# DSPLIT.net
KiCad netlist of a schematic drawn in EAGLE
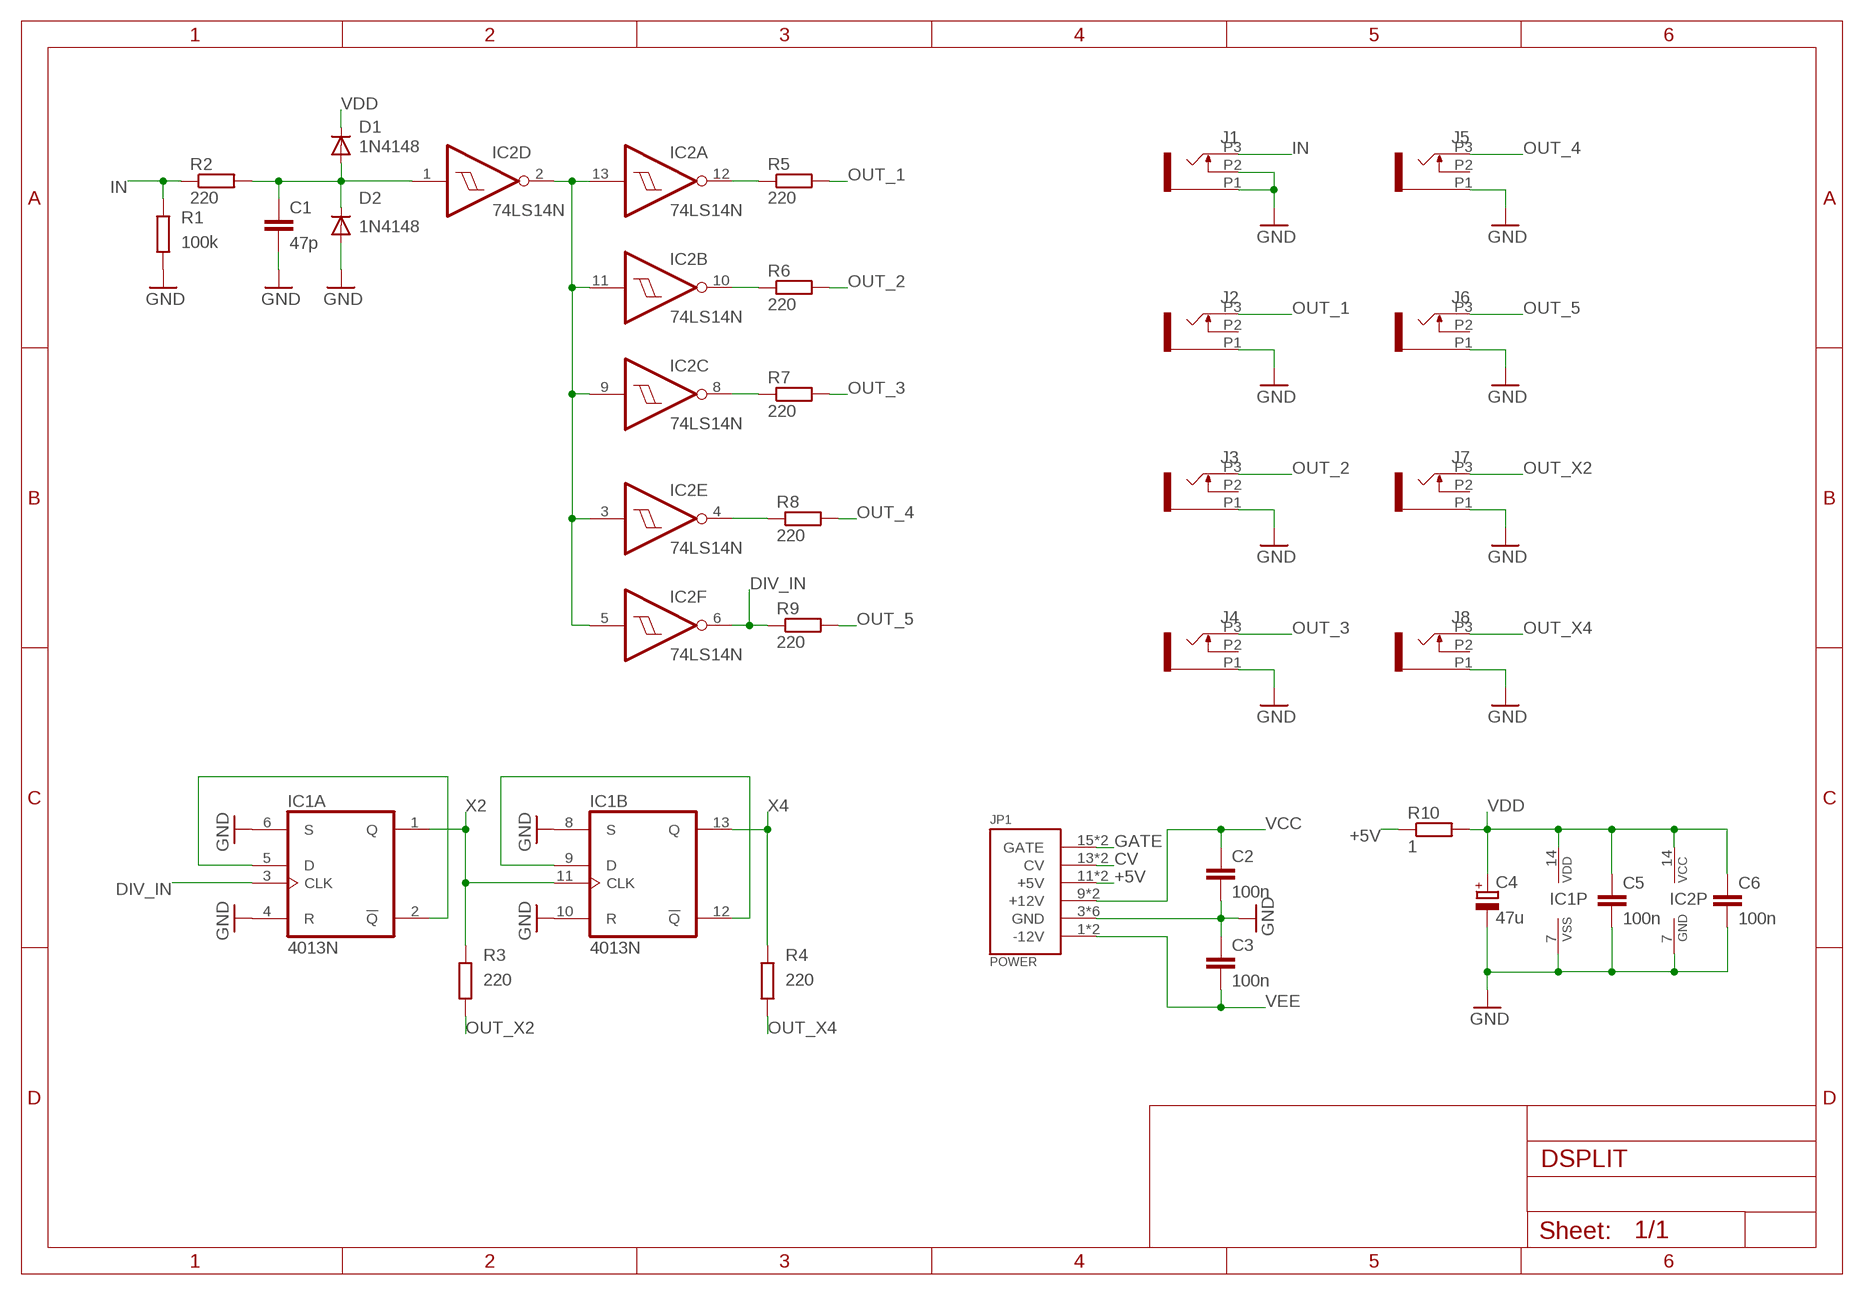
[diagram p0: schematic, sheet 1]

(export (version "E")
  (design (tool "Eeschema 10.0.6"))
  (components
    (comp (ref "C1")
      (value "47p")
      (footprint "eagle-import:C050-024X044")
      (libsource (lib "eagle-import") (part "C-EU050-024X044"))
    )
    (comp (ref "C2")
      (value "100n")
      (footprint "eagle-import:C050-024X044")
      (libsource (lib "eagle-import") (part "C-EU050-024X044"))
    )
    (comp (ref "C3")
      (value "100n")
      (footprint "eagle-import:C050-024X044")
      (libsource (lib "eagle-import") (part "C-EU050-024X044"))
    )
    (comp (ref "C4")
      (value "47u")
      (footprint "eagle-import:E2,5-6")
      (libsource (lib "eagle-import") (part "CPOL-EUE2.5-6"))
    )
    (comp (ref "C5")
      (value "100n")
      (footprint "eagle-import:C050-024X044")
      (libsource (lib "eagle-import") (part "C-EU050-024X044"))
    )
    (comp (ref "C6")
      (value "100n")
      (footprint "eagle-import:C050-024X044")
      (libsource (lib "eagle-import") (part "C-EU050-024X044"))
    )
    (comp (ref "D1")
      (value "1N4148")
      (footprint "eagle-import:DO35-7")
      (libsource (lib "eagle-import") (part "1N4148DO35-7"))
    )
    (comp (ref "D2")
      (value "1N4148")
      (footprint "eagle-import:DO35-7")
      (libsource (lib "eagle-import") (part "1N4148DO35-7"))
    )
    (comp (ref "IC1")
      (value "4013N")
      (footprint "eagle-import:DIL14")
      (libsource (lib "eagle-import") (part "4013N"))
    )
    (comp (ref "IC2")
      (value "74LS14N")
      (footprint "eagle-import:DIL14")
      (libsource (lib "eagle-import") (part "7414NLS"))
    )
    (comp (ref "J1")
      (value "WQP-PJ302M_JACK")
      (footprint "eagle-import:WQP-PJ302M_JACK")
      (libsource (lib "eagle-import") (part "WQP-PJ302M_JACK"))
    )
    (comp (ref "J2")
      (value "WQP-PJ302M_JACK")
      (footprint "eagle-import:WQP-PJ302M_JACK")
      (libsource (lib "eagle-import") (part "WQP-PJ302M_JACK"))
    )
    (comp (ref "J3")
      (value "WQP-PJ302M_JACK")
      (footprint "eagle-import:WQP-PJ302M_JACK")
      (libsource (lib "eagle-import") (part "WQP-PJ302M_JACK"))
    )
    (comp (ref "J4")
      (value "WQP-PJ302M_JACK")
      (footprint "eagle-import:WQP-PJ302M_JACK")
      (libsource (lib "eagle-import") (part "WQP-PJ302M_JACK"))
    )
    (comp (ref "J5")
      (value "WQP-PJ302M_JACK")
      (footprint "eagle-import:WQP-PJ302M_JACK")
      (libsource (lib "eagle-import") (part "WQP-PJ302M_JACK"))
    )
    (comp (ref "J6")
      (value "WQP-PJ302M_JACK")
      (footprint "eagle-import:WQP-PJ302M_JACK")
      (libsource (lib "eagle-import") (part "WQP-PJ302M_JACK"))
    )
    (comp (ref "J7")
      (value "WQP-PJ302M_JACK")
      (footprint "eagle-import:WQP-PJ302M_JACK")
      (libsource (lib "eagle-import") (part "WQP-PJ302M_JACK"))
    )
    (comp (ref "J8")
      (value "WQP-PJ302M_JACK")
      (footprint "eagle-import:WQP-PJ302M_JACK")
      (libsource (lib "eagle-import") (part "WQP-PJ302M_JACK"))
    )
    (comp (ref "JP1")
      (value "POWER")
      (footprint "eagle-import:POWER_16")
      (libsource (lib "eagle-import") (part "POWER{dblquote}"))
    )
    (comp (ref "R1")
      (value "100k")
      (footprint "eagle-import:0204_7")
      (libsource (lib "eagle-import") (part "R-EU_0204/7"))
    )
    (comp (ref "R2")
      (value "220")
      (footprint "eagle-import:0204_7")
      (libsource (lib "eagle-import") (part "R-EU_0204/7"))
    )
    (comp (ref "R3")
      (value "220")
      (footprint "eagle-import:0204_7")
      (libsource (lib "eagle-import") (part "R-EU_0204/7"))
    )
    (comp (ref "R4")
      (value "220")
      (footprint "eagle-import:0204_7")
      (libsource (lib "eagle-import") (part "R-EU_0204/7"))
    )
    (comp (ref "R5")
      (value "220")
      (footprint "eagle-import:0204_7")
      (libsource (lib "eagle-import") (part "R-EU_0204/7"))
    )
    (comp (ref "R6")
      (value "220")
      (footprint "eagle-import:0204_7")
      (libsource (lib "eagle-import") (part "R-EU_0204/7"))
    )
    (comp (ref "R7")
      (value "220")
      (footprint "eagle-import:0204_7")
      (libsource (lib "eagle-import") (part "R-EU_0204/7"))
    )
    (comp (ref "R8")
      (value "220")
      (footprint "eagle-import:0204_7")
      (libsource (lib "eagle-import") (part "R-EU_0204/7"))
    )
    (comp (ref "R9")
      (value "220")
      (footprint "eagle-import:0204_7")
      (libsource (lib "eagle-import") (part "R-EU_0204/7"))
    )
    (comp (ref "R10")
      (value "1")
      (footprint "eagle-import:0204_7")
      (libsource (lib "eagle-import") (part "R-EU_0204/7"))
    )
  )
  (nets
    (net (code "1") (name "/+5V") (class "Default")
      (node (ref "JP1") (pin "11") (pinfunction "+5V_11") (pintype "bidirectional"))
      (node (ref "JP1") (pin "12") (pinfunction "+5V_12") (pintype "bidirectional"))
      (node (ref "R10") (pin "1") (pinfunction "1_1") (pintype "passive"))
    )
    (net (code "2") (name "/CV") (class "Default")
      (node (ref "JP1") (pin "13") (pinfunction "CV_13") (pintype "bidirectional"))
      (node (ref "JP1") (pin "14") (pinfunction "CV_14") (pintype "bidirectional"))
    )
    (net (code "3") (name "/DIV_IN") (class "Default")
      (node (ref "IC1") (pin "3") (pinfunction "CLK_3") (pintype "input"))
      (node (ref "IC2") (pin "6") (pinfunction "O_6") (pintype "output"))
      (node (ref "R9") (pin "1") (pinfunction "1_1") (pintype "passive"))
    )
    (net (code "4") (name "/GATE") (class "Default")
      (node (ref "JP1") (pin "15") (pinfunction "GATE_15") (pintype "bidirectional"))
      (node (ref "JP1") (pin "16") (pinfunction "GATE_16") (pintype "bidirectional"))
    )
    (net (code "5") (name "/IN") (class "Default")
      (node (ref "J1") (pin "P3") (pinfunction "3_P3") (pintype "passive"))
      (node (ref "R1") (pin "2") (pinfunction "2_2") (pintype "passive"))
      (node (ref "R2") (pin "1") (pinfunction "1_1") (pintype "passive"))
    )
    (net (code "6") (name "/OUT_1") (class "Default")
      (node (ref "J2") (pin "P3") (pinfunction "3_P3") (pintype "passive"))
      (node (ref "R5") (pin "2") (pinfunction "2_2") (pintype "passive"))
    )
    (net (code "7") (name "/OUT_2") (class "Default")
      (node (ref "J3") (pin "P3") (pinfunction "3_P3") (pintype "passive"))
      (node (ref "R6") (pin "2") (pinfunction "2_2") (pintype "passive"))
    )
    (net (code "8") (name "/OUT_3") (class "Default")
      (node (ref "J4") (pin "P3") (pinfunction "3_P3") (pintype "passive"))
      (node (ref "R7") (pin "2") (pinfunction "2_2") (pintype "passive"))
    )
    (net (code "9") (name "/OUT_4") (class "Default")
      (node (ref "J5") (pin "P3") (pinfunction "3_P3") (pintype "passive"))
      (node (ref "R8") (pin "2") (pinfunction "2_2") (pintype "passive"))
    )
    (net (code "10") (name "/OUT_5") (class "Default")
      (node (ref "J6") (pin "P3") (pinfunction "3_P3") (pintype "passive"))
      (node (ref "R9") (pin "2") (pinfunction "2_2") (pintype "passive"))
    )
    (net (code "11") (name "/OUT_X2") (class "Default")
      (node (ref "J7") (pin "P3") (pinfunction "3_P3") (pintype "passive"))
      (node (ref "R3") (pin "2") (pinfunction "2_2") (pintype "passive"))
    )
    (net (code "12") (name "/OUT_X4") (class "Default")
      (node (ref "J8") (pin "P3") (pinfunction "3_P3") (pintype "passive"))
      (node (ref "R4") (pin "2") (pinfunction "2_2") (pintype "passive"))
    )
    (net (code "13") (name "/VCC") (class "Default")
      (node (ref "C2") (pin "1") (pinfunction "1_1") (pintype "passive"))
      (node (ref "JP1") (pin "10") (pinfunction "+12V_10") (pintype "bidirectional"))
      (node (ref "JP1") (pin "9") (pinfunction "+12V_9") (pintype "bidirectional"))
    )
    (net (code "14") (name "/VDD") (class "Default")
      (node (ref "C4") (pin "+") (pinfunction "+_+") (pintype "passive"))
      (node (ref "C5") (pin "1") (pinfunction "1_1") (pintype "passive"))
      (node (ref "C6") (pin "1") (pinfunction "1_1") (pintype "passive"))
      (node (ref "D1") (pin "C") (pinfunction "C_C") (pintype "passive"))
      (node (ref "IC1") (pin "14") (pinfunction "VDD_14") (pintype "power_in"))
      (node (ref "IC2") (pin "14") (pinfunction "VCC_14") (pintype "power_in"))
      (node (ref "R10") (pin "2") (pinfunction "2_2") (pintype "passive"))
    )
    (net (code "15") (name "/VEE") (class "Default")
      (node (ref "C3") (pin "2") (pinfunction "2_2") (pintype "passive"))
      (node (ref "JP1") (pin "1") (pinfunction "-12V_1") (pintype "bidirectional"))
      (node (ref "JP1") (pin "2") (pinfunction "-12V_2") (pintype "bidirectional"))
    )
    (net (code "16") (name "/X2") (class "Default")
      (node (ref "IC1") (pin "1") (pinfunction "Q_1") (pintype "output"))
      (node (ref "IC1") (pin "11") (pinfunction "CLK_11") (pintype "input"))
      (node (ref "R3") (pin "1") (pinfunction "1_1") (pintype "passive"))
    )
    (net (code "17") (name "/X4") (class "Default")
      (node (ref "IC1") (pin "13") (pinfunction "Q_13") (pintype "output"))
      (node (ref "R4") (pin "1") (pinfunction "1_1") (pintype "passive"))
    )
    (net (code "18") (name "GND") (class "Default")
      (node (ref "C1") (pin "2") (pinfunction "2_2") (pintype "passive"))
      (node (ref "C2") (pin "2") (pinfunction "2_2") (pintype "passive"))
      (node (ref "C3") (pin "1") (pinfunction "1_1") (pintype "passive"))
      (node (ref "C4") (pin "-") (pinfunction "-_-") (pintype "passive"))
      (node (ref "C5") (pin "2") (pinfunction "2_2") (pintype "passive"))
      (node (ref "C6") (pin "2") (pinfunction "2_2") (pintype "passive"))
      (node (ref "D2") (pin "A") (pinfunction "A_A") (pintype "passive"))
      (node (ref "IC1") (pin "10") (pinfunction "R_10") (pintype "input"))
      (node (ref "IC1") (pin "4") (pinfunction "R_4") (pintype "input"))
      (node (ref "IC1") (pin "6") (pinfunction "S_6") (pintype "input"))
      (node (ref "IC1") (pin "7") (pinfunction "VSS_7") (pintype "power_in"))
      (node (ref "IC1") (pin "8") (pinfunction "S_8") (pintype "input"))
      (node (ref "IC2") (pin "7") (pinfunction "GND_7") (pintype "power_in"))
      (node (ref "J1") (pin "P1") (pinfunction "1_P1") (pintype "passive"))
      (node (ref "J1") (pin "P2") (pinfunction "2_P2") (pintype "passive"))
      (node (ref "J2") (pin "P1") (pinfunction "1_P1") (pintype "passive"))
      (node (ref "J3") (pin "P1") (pinfunction "1_P1") (pintype "passive"))
      (node (ref "J4") (pin "P1") (pinfunction "1_P1") (pintype "passive"))
      (node (ref "J5") (pin "P1") (pinfunction "1_P1") (pintype "passive"))
      (node (ref "J6") (pin "P1") (pinfunction "1_P1") (pintype "passive"))
      (node (ref "J7") (pin "P1") (pinfunction "1_P1") (pintype "passive"))
      (node (ref "J8") (pin "P1") (pinfunction "1_P1") (pintype "passive"))
      (node (ref "JP1") (pin "3") (pinfunction "GND_3") (pintype "bidirectional"))
      (node (ref "JP1") (pin "4") (pinfunction "GND_4") (pintype "bidirectional"))
      (node (ref "JP1") (pin "5") (pinfunction "GND_5") (pintype "bidirectional"))
      (node (ref "JP1") (pin "6") (pinfunction "GND_6") (pintype "bidirectional"))
      (node (ref "JP1") (pin "7") (pinfunction "GND_7") (pintype "bidirectional"))
      (node (ref "JP1") (pin "8") (pinfunction "GND_8") (pintype "bidirectional"))
      (node (ref "R1") (pin "1") (pinfunction "1_1") (pintype "passive"))
    )
    (net (code "19") (name "Net-(IC1A-D)") (class "Default")
      (node (ref "IC1") (pin "2") (pinfunction "~{Q}_2") (pintype "output"))
      (node (ref "IC1") (pin "5") (pinfunction "D_5") (pintype "input"))
    )
    (net (code "20") (name "Net-(IC1B-D)") (class "Default")
      (node (ref "IC1") (pin "12") (pinfunction "~{Q}_12") (pintype "output"))
      (node (ref "IC1") (pin "9") (pinfunction "D_9") (pintype "input"))
    )
    (net (code "21") (name "Net-(IC2A-I)") (class "Default")
      (node (ref "IC2") (pin "11") (pinfunction "I_11") (pintype "input"))
      (node (ref "IC2") (pin "13") (pinfunction "I_13") (pintype "input"))
      (node (ref "IC2") (pin "2") (pinfunction "O_2") (pintype "output"))
      (node (ref "IC2") (pin "3") (pinfunction "I_3") (pintype "input"))
      (node (ref "IC2") (pin "5") (pinfunction "I_5") (pintype "input"))
      (node (ref "IC2") (pin "9") (pinfunction "I_9") (pintype "input"))
    )
    (net (code "22") (name "Net-(IC2A-O)") (class "Default")
      (node (ref "IC2") (pin "12") (pinfunction "O_12") (pintype "output"))
      (node (ref "R5") (pin "1") (pinfunction "1_1") (pintype "passive"))
    )
    (net (code "23") (name "Net-(IC2B-O)") (class "Default")
      (node (ref "IC2") (pin "10") (pinfunction "O_10") (pintype "output"))
      (node (ref "R6") (pin "1") (pinfunction "1_1") (pintype "passive"))
    )
    (net (code "24") (name "Net-(IC2C-O)") (class "Default")
      (node (ref "IC2") (pin "8") (pinfunction "O_8") (pintype "output"))
      (node (ref "R7") (pin "1") (pinfunction "1_1") (pintype "passive"))
    )
    (net (code "25") (name "Net-(IC2D-I)") (class "Default")
      (node (ref "C1") (pin "1") (pinfunction "1_1") (pintype "passive"))
      (node (ref "D1") (pin "A") (pinfunction "A_A") (pintype "passive"))
      (node (ref "D2") (pin "C") (pinfunction "C_C") (pintype "passive"))
      (node (ref "IC2") (pin "1") (pinfunction "I_1") (pintype "input"))
      (node (ref "R2") (pin "2") (pinfunction "2_2") (pintype "passive"))
    )
    (net (code "26") (name "Net-(IC2E-O)") (class "Default")
      (node (ref "IC2") (pin "4") (pinfunction "O_4") (pintype "output"))
      (node (ref "R8") (pin "1") (pinfunction "1_1") (pintype "passive"))
    )
    (net (code "27") (name "unconnected-(J2-2-PadP2)") (class "Default")
      (node (ref "J2") (pin "P2") (pinfunction "2_P2") (pintype "passive"))
    )
    (net (code "28") (name "unconnected-(J3-2-PadP2)") (class "Default")
      (node (ref "J3") (pin "P2") (pinfunction "2_P2") (pintype "passive"))
    )
    (net (code "29") (name "unconnected-(J4-2-PadP2)") (class "Default")
      (node (ref "J4") (pin "P2") (pinfunction "2_P2") (pintype "passive"))
    )
    (net (code "30") (name "unconnected-(J5-2-PadP2)") (class "Default")
      (node (ref "J5") (pin "P2") (pinfunction "2_P2") (pintype "passive"))
    )
    (net (code "31") (name "unconnected-(J6-2-PadP2)") (class "Default")
      (node (ref "J6") (pin "P2") (pinfunction "2_P2") (pintype "passive"))
    )
    (net (code "32") (name "unconnected-(J7-2-PadP2)") (class "Default")
      (node (ref "J7") (pin "P2") (pinfunction "2_P2") (pintype "passive"))
    )
    (net (code "33") (name "unconnected-(J8-2-PadP2)") (class "Default")
      (node (ref "J8") (pin "P2") (pinfunction "2_P2") (pintype "passive"))
    )
  )
)
